# VOC_Board.net
KiCad netlist of a schematic drawn in Altium Designer
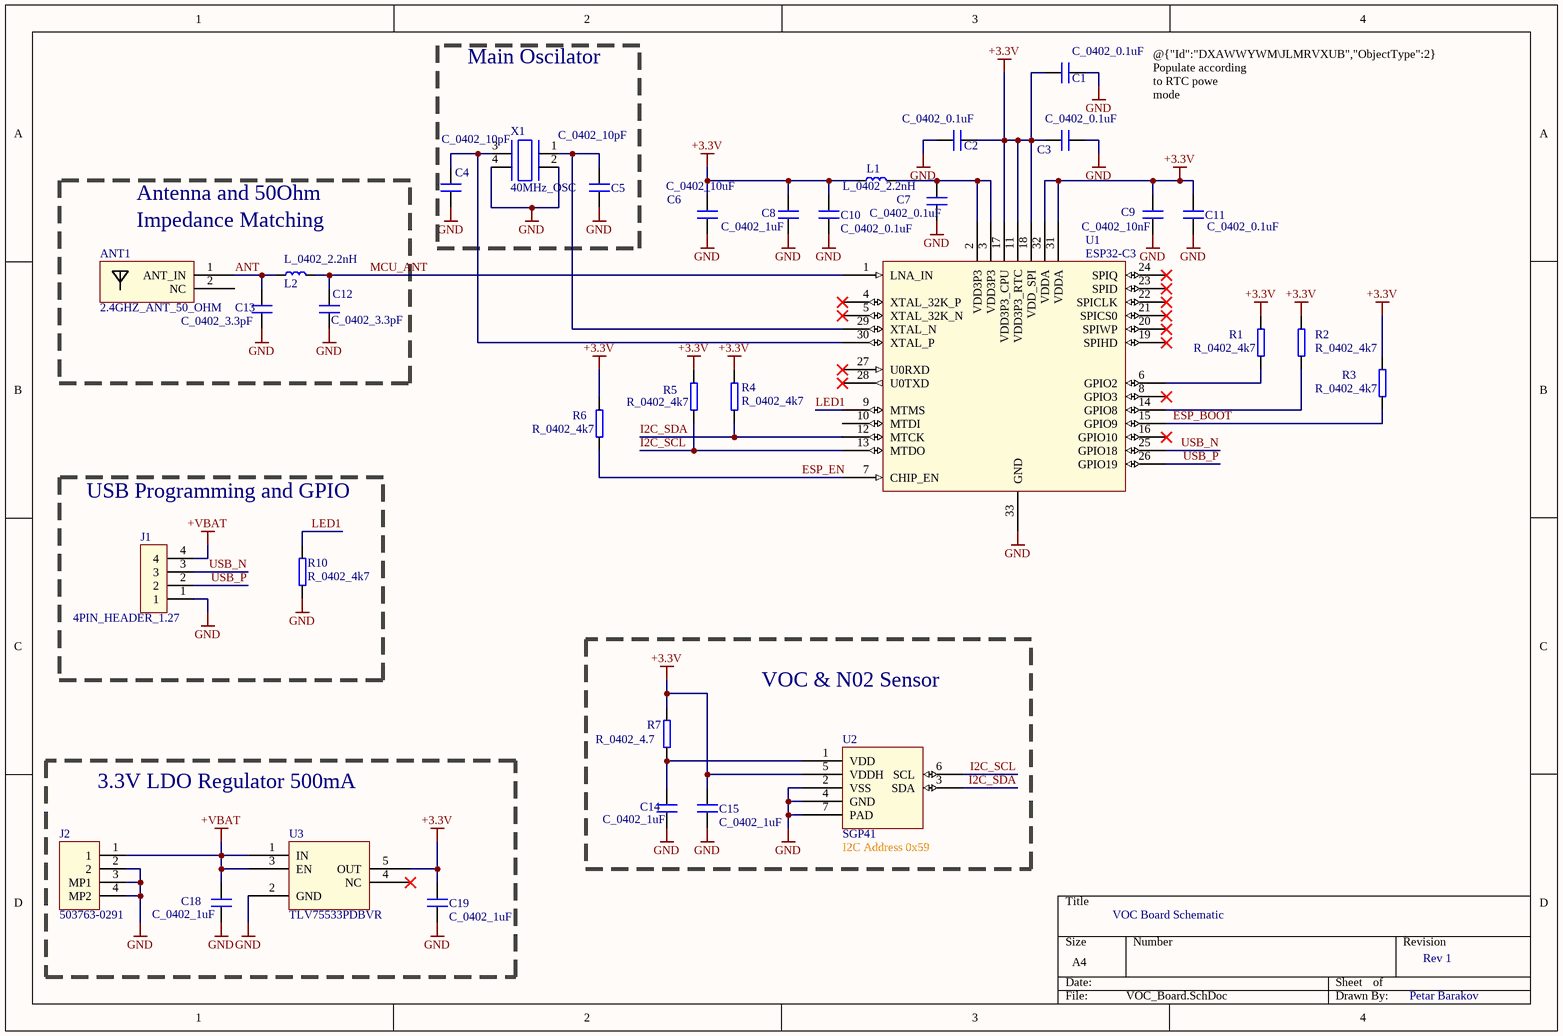
[diagram p0: VOC_Board.SchDoc]

(export (version "E")
  (design (tool "Eeschema 10.0.6"))
  (components
    (comp (ref "ANT1")
      (value "2.4GHZ_ANT_50_OHM")
      (footprint "Chip2PinSM127P600-8N")
      (description "2.4GHz Chip Antenna 50 Ohm Impedance ANT2012LL00R2400A")
      (libsource (lib "Petar B") (part "2.4GHZ_ANT_50_OHM"))
    )
    (comp (ref "C1")
      (value "C_0402_0.1uF")
      (footprint "C_0402")
      (fields (field (name "JLC PART NUMBER") "C1525"))
      (libsource (lib "Petar B") (part "Cap_symbol"))
    )
    (comp (ref "C2")
      (value "C_0402_0.1uF")
      (footprint "C_0402")
      (fields (field (name "JLC PART NUMBER") "C1525"))
      (libsource (lib "Petar B") (part "Cap_symbol"))
    )
    (comp (ref "C3")
      (value "C_0402_0.1uF")
      (footprint "C_0402")
      (fields (field (name "JLC PART NUMBER") "C1525"))
      (libsource (lib "Petar B") (part "Cap_symbol"))
    )
    (comp (ref "C4")
      (value "C_0402_10pF")
      (footprint "C_0402")
      (fields (field (name "JLC PART NUMBER") "C32949"))
      (libsource (lib "Petar B") (part "Cap_symbol"))
    )
    (comp (ref "C5")
      (value "C_0402_10pF")
      (footprint "C_0402")
      (fields (field (name "JLC PART NUMBER") "C32949"))
      (libsource (lib "Petar B") (part "Cap_symbol"))
    )
    (comp (ref "C6")
      (value "C_0402_10uF")
      (footprint "C_0402")
      (fields (field (name "JLC PART NUMBER") "C15525"))
      (libsource (lib "Petar B") (part "Cap_symbol"))
    )
    (comp (ref "C7")
      (value "C_0402_0.1uF")
      (footprint "C_0402")
      (fields (field (name "JLC PART NUMBER") "C1525"))
      (libsource (lib "Petar B") (part "Cap_symbol"))
    )
    (comp (ref "C8")
      (value "C_0402_1uF")
      (footprint "C_0402")
      (fields (field (name "JLC PART NUMBER") "C52923"))
      (libsource (lib "Petar B") (part "Cap_symbol"))
    )
    (comp (ref "C9")
      (value "C_0402_10nF")
      (footprint "C_0402")
      (fields (field (name "JLC PART NUMBER") "C15195"))
      (libsource (lib "Petar B") (part "Cap_symbol"))
    )
    (comp (ref "C10")
      (value "C_0402_0.1uF")
      (footprint "C_0402")
      (fields (field (name "JLC PART NUMBER") "C1525"))
      (libsource (lib "Petar B") (part "Cap_symbol"))
    )
    (comp (ref "C11")
      (value "C_0402_0.1uF")
      (footprint "C_0402")
      (fields (field (name "JLC PART NUMBER") "C1525"))
      (libsource (lib "Petar B") (part "Cap_symbol"))
    )
    (comp (ref "C12")
      (value "C_0402_3.3pF")
      (footprint "C_0402")
      (fields (field (name "JLC PART NUMBER") "C326841"))
      (libsource (lib "Petar B") (part "Cap_symbol"))
    )
    (comp (ref "C13")
      (value "C_0402_3.3pF")
      (footprint "C_0402")
      (fields (field (name "JLC PART NUMBER") "C326841"))
      (libsource (lib "Petar B") (part "Cap_symbol"))
    )
    (comp (ref "C14")
      (value "C_0402_1uF")
      (footprint "C_0402")
      (fields (field (name "JLC PART NUMBER") "C52923"))
      (libsource (lib "Petar B") (part "Cap_symbol"))
    )
    (comp (ref "C15")
      (value "C_0402_1uF")
      (footprint "C_0402")
      (fields (field (name "JLC PART NUMBER") "C52923"))
      (libsource (lib "Petar B") (part "Cap_symbol"))
    )
    (comp (ref "C18")
      (value "C_0402_1uF")
      (footprint "C_0402")
      (fields (field (name "JLC PART NUMBER") "C52923"))
      (libsource (lib "Petar B") (part "Cap_symbol"))
    )
    (comp (ref "C19")
      (value "C_0402_1uF")
      (footprint "C_0402")
      (fields (field (name "JLC PART NUMBER") "C52923"))
      (libsource (lib "Petar B") (part "Cap_symbol"))
    )
    (comp (ref "J1")
      (value "4PIN_HEADER_1.27")
      (footprint "4PIN_HEADER_1.27-Footprint-1")
      (libsource (lib "Petar B") (part "4PIN_HEADER_1.27-Symbol-1"))
    )
    (comp (ref "J2")
      (value "503763-0291")
      (footprint "Molex 503763-0291")
      (description "Molex 503763-0291")
      (libsource (lib "Petar B") (part "503763-0291"))
    )
    (comp (ref "L1")
      (value "L_0402_2.2nH")
      (footprint "L_0402")
      (fields (field (name "JLC PART NUMBER") "C92035"))
      (libsource (lib "Petar B") (part "Ind_Symbol"))
    )
    (comp (ref "L2")
      (value "L_0402_2.2nH")
      (footprint "L_0402")
      (fields (field (name "JLC PART NUMBER") "C92035"))
      (libsource (lib "Petar B") (part "Ind_Symbol"))
    )
    (comp (ref "R1")
      (value "R_0402_4k7")
      (footprint "R_0402")
      (fields (field (name "JLC PART NUMBER") "C25900"))
      (libsource (lib "Petar B") (part "R_symbol"))
    )
    (comp (ref "R2")
      (value "R_0402_4k7")
      (footprint "R_0402")
      (fields (field (name "JLC PART NUMBER") "C25900"))
      (libsource (lib "Petar B") (part "R_symbol"))
    )
    (comp (ref "R3")
      (value "R_0402_4k7")
      (footprint "R_0402")
      (fields (field (name "JLC PART NUMBER") "C25900"))
      (libsource (lib "Petar B") (part "R_symbol"))
    )
    (comp (ref "R4")
      (value "R_0402_4k7")
      (footprint "R_0402")
      (fields (field (name "JLC PART NUMBER") "C25900"))
      (libsource (lib "Petar B") (part "R_symbol"))
    )
    (comp (ref "R5")
      (value "R_0402_4k7")
      (footprint "R_0402")
      (fields (field (name "JLC PART NUMBER") "C25900"))
      (libsource (lib "Petar B") (part "R_symbol"))
    )
    (comp (ref "R6")
      (value "R_0402_4k7")
      (footprint "R_0402")
      (fields (field (name "JLC PART NUMBER") "C25900"))
      (libsource (lib "Petar B") (part "R_symbol"))
    )
    (comp (ref "R7")
      (value "R_0402_4.7")
      (footprint "R_0402")
      (fields (field (name "JLC PART NUMBER") "C137962"))
      (libsource (lib "Petar B") (part "R_symbol"))
    )
    (comp (ref "R10")
      (value "R_0402_4k7")
      (footprint "R_0402")
      (fields (field (name "JLC PART NUMBER") "C25900"))
      (libsource (lib "Petar B") (part "R_symbol"))
    )
    (comp (ref "U1")
      (value "ESP32-C3")
      (footprint "QFN127P600-8N")
      (description "33 pin ESP32_C3 Microcontroller")
      (fields (field (name "JLC PART NUMBER") "C2858491"))
      (libsource (lib "Petar B") (part "ESP32-C3_symbol"))
    )
    (comp (ref "U2")
      (value "SGP41")
      (footprint "SGP41-D-R4-Footprint-2")
      (description "Air Quality Sensors VOC and NOx (MOX) Gas Pollutant Sensor")
      (fields (field (name "JLC PART NUMBER") "C3659325"))
      (libsource (lib "Petar B") (part "SGP41"))
    )
    (comp (ref "U3")
      (value "TLV75533PDBVR")
      (footprint "SOT95P280X145-5N")
      (fields (field (name "JLC PART NUMBER") "C404027"))
      (libsource (lib "Petar B") (part "TLV75533PDBVR-Symbol"))
    )
    (comp (ref "X1")
      (value "40MHz_OSC")
      (footprint "40MHz_OSC-Footprint-1")
      (description "40 MHZ Oscillator, 10pF load capacitance")
      (fields (field (name "JLC PART NUMBER") "C426988"))
      (libsource (lib "Petar B") (part "OSC_SYMB"))
    )
  )
  (nets
    (net (code "1") (name "+3.3V") (class "Default")
      (node (ref "C1") (pin "1") (pinfunction "1_1") (pintype "passive"))
      (node (ref "C10") (pin "1") (pinfunction "1_1") (pintype "passive"))
      (node (ref "C11") (pin "2") (pinfunction "2_2") (pintype "passive"))
      (node (ref "C15") (pin "2") (pinfunction "2_2") (pintype "passive"))
      (node (ref "C19") (pin "2") (pinfunction "2_2") (pintype "passive"))
      (node (ref "C2") (pin "2") (pinfunction "2_2") (pintype "passive"))
      (node (ref "C3") (pin "1") (pinfunction "1_1") (pintype "passive"))
      (node (ref "C6") (pin "2") (pinfunction "2_2") (pintype "passive"))
      (node (ref "C8") (pin "2") (pinfunction "2_2") (pintype "passive"))
      (node (ref "C9") (pin "2") (pinfunction "2_2") (pintype "passive"))
      (node (ref "L1") (pin "1") (pinfunction "1_1") (pintype "passive"))
      (node (ref "R1") (pin "1") (pinfunction "1_1") (pintype "passive"))
      (node (ref "R2") (pin "1") (pinfunction "1_1") (pintype "passive"))
      (node (ref "R3") (pin "1") (pinfunction "1_1") (pintype "passive"))
      (node (ref "R4") (pin "1") (pinfunction "1_1") (pintype "passive"))
      (node (ref "R5") (pin "1") (pinfunction "1_1") (pintype "passive"))
      (node (ref "R6") (pin "1") (pinfunction "1_1") (pintype "passive"))
      (node (ref "R7") (pin "1") (pinfunction "1_1") (pintype "passive"))
      (node (ref "U1") (pin "11") (pinfunction "VDD3P3_RTC_11") (pintype "power_in"))
      (node (ref "U1") (pin "17") (pinfunction "VDD3P3_CPU_17") (pintype "power_in"))
      (node (ref "U1") (pin "18") (pinfunction "VDD_SPI_18") (pintype "power_in"))
      (node (ref "U1") (pin "31") (pinfunction "VDDA_31") (pintype "power_in"))
      (node (ref "U1") (pin "32") (pinfunction "VDDA_32") (pintype "power_in"))
      (node (ref "U2") (pin "5") (pinfunction "VDDH_5") (pintype "power_in"))
      (node (ref "U3") (pin "5") (pinfunction "OUT_5") (pintype "passive"))
    )
    (net (code "2") (name "+VBAT") (class "Default")
      (node (ref "C18") (pin "2") (pinfunction "2_2") (pintype "passive"))
      (node (ref "J1") (pin "4") (pinfunction "4_4") (pintype "passive"))
      (node (ref "J2") (pin "1") (pinfunction "1_1") (pintype "passive"))
      (node (ref "U3") (pin "1") (pinfunction "IN_1") (pintype "passive"))
      (node (ref "U3") (pin "3") (pinfunction "EN_3") (pintype "passive"))
    )
    (net (code "3") (name "/ANT") (class "Default")
      (node (ref "ANT1") (pin "1") (pinfunction "ANT_IN_1") (pintype "passive"))
      (node (ref "C13") (pin "2") (pinfunction "2_2") (pintype "passive"))
      (node (ref "L2") (pin "1") (pinfunction "1_1") (pintype "passive"))
    )
    (net (code "4") (name "/ESP_BOOT") (class "Default")
      (node (ref "R3") (pin "2") (pinfunction "2_2") (pintype "passive"))
      (node (ref "U1") (pin "15") (pinfunction "GPIO9_15") (pintype "bidirectional"))
    )
    (net (code "5") (name "/ESP_EN") (class "Default")
      (node (ref "R6") (pin "2") (pinfunction "2_2") (pintype "passive"))
      (node (ref "U1") (pin "7") (pinfunction "CHIP_EN_7") (pintype "input"))
    )
    (net (code "6") (name "/I2C_SCL") (class "Default")
      (node (ref "R5") (pin "2") (pinfunction "2_2") (pintype "passive"))
      (node (ref "U1") (pin "13") (pinfunction "MTDO_13") (pintype "bidirectional"))
      (node (ref "U2") (pin "6") (pinfunction "SCL_6") (pintype "bidirectional"))
    )
    (net (code "7") (name "/I2C_SDA") (class "Default")
      (node (ref "R4") (pin "2") (pinfunction "2_2") (pintype "passive"))
      (node (ref "U1") (pin "12") (pinfunction "MTCK_12") (pintype "bidirectional"))
      (node (ref "U2") (pin "3") (pinfunction "SDA_3") (pintype "bidirectional"))
    )
    (net (code "8") (name "/LED1") (class "Default")
      (node (ref "R10") (pin "1") (pinfunction "1_1") (pintype "passive"))
      (node (ref "U1") (pin "9") (pinfunction "MTMS_9") (pintype "bidirectional"))
    )
    (net (code "9") (name "/MCU_ANT") (class "Default")
      (node (ref "C12") (pin "2") (pinfunction "2_2") (pintype "passive"))
      (node (ref "L2") (pin "2") (pinfunction "2_2") (pintype "passive"))
      (node (ref "U1") (pin "1") (pinfunction "LNA_IN_1") (pintype "input"))
    )
    (net (code "10") (name "/USB_N") (class "Default")
      (node (ref "J1") (pin "3") (pinfunction "3_3") (pintype "passive"))
      (node (ref "U1") (pin "25") (pinfunction "GPIO18_25") (pintype "bidirectional"))
    )
    (net (code "11") (name "/USB_P") (class "Default")
      (node (ref "J1") (pin "2") (pinfunction "2_2") (pintype "passive"))
      (node (ref "U1") (pin "26") (pinfunction "GPIO19_26") (pintype "bidirectional"))
    )
    (net (code "12") (name "GND") (class "Default")
      (node (ref "C1") (pin "2") (pinfunction "2_2") (pintype "passive"))
      (node (ref "C10") (pin "2") (pinfunction "2_2") (pintype "passive"))
      (node (ref "C11") (pin "1") (pinfunction "1_1") (pintype "passive"))
      (node (ref "C12") (pin "1") (pinfunction "1_1") (pintype "passive"))
      (node (ref "C13") (pin "1") (pinfunction "1_1") (pintype "passive"))
      (node (ref "C14") (pin "1") (pinfunction "1_1") (pintype "passive"))
      (node (ref "C15") (pin "1") (pinfunction "1_1") (pintype "passive"))
      (node (ref "C18") (pin "1") (pinfunction "1_1") (pintype "passive"))
      (node (ref "C19") (pin "1") (pinfunction "1_1") (pintype "passive"))
      (node (ref "C2") (pin "1") (pinfunction "1_1") (pintype "passive"))
      (node (ref "C3") (pin "2") (pinfunction "2_2") (pintype "passive"))
      (node (ref "C4") (pin "1") (pinfunction "1_1") (pintype "passive"))
      (node (ref "C5") (pin "1") (pinfunction "1_1") (pintype "passive"))
      (node (ref "C6") (pin "1") (pinfunction "1_1") (pintype "passive"))
      (node (ref "C7") (pin "2") (pinfunction "2_2") (pintype "passive"))
      (node (ref "C8") (pin "1") (pinfunction "1_1") (pintype "passive"))
      (node (ref "C9") (pin "1") (pinfunction "1_1") (pintype "passive"))
      (node (ref "J1") (pin "1") (pinfunction "1_1") (pintype "passive"))
      (node (ref "J2") (pin "2") (pinfunction "2_2") (pintype "passive"))
      (node (ref "J2") (pin "3") (pinfunction "MP1_3") (pintype "passive"))
      (node (ref "J2") (pin "4") (pinfunction "MP2_4") (pintype "passive"))
      (node (ref "R10") (pin "2") (pinfunction "2_2") (pintype "passive"))
      (node (ref "U1") (pin "33") (pinfunction "GND_33") (pintype "power_in"))
      (node (ref "U2") (pin "2") (pinfunction "VSS_2") (pintype "power_in"))
      (node (ref "U2") (pin "4") (pinfunction "GND_4") (pintype "passive"))
      (node (ref "U2") (pin "7") (pinfunction "PAD_7") (pintype "passive"))
      (node (ref "U3") (pin "2") (pinfunction "GND_2") (pintype "passive"))
      (node (ref "X1") (pin "2") (pinfunction "2_2") (pintype "passive"))
      (node (ref "X1") (pin "4") (pinfunction "4_4") (pintype "passive"))
    )
    (net (code "13") (name "Net-(C7-Pad1)") (class "Default")
      (node (ref "C7") (pin "1") (pinfunction "1_1") (pintype "passive"))
      (node (ref "L1") (pin "2") (pinfunction "2_2") (pintype "passive"))
      (node (ref "U1") (pin "2") (pinfunction "VDD3P3_2") (pintype "power_in"))
      (node (ref "U1") (pin "3") (pinfunction "VDD3P3_3") (pintype "power_in"))
    )
    (net (code "14") (name "Net-(U1-GPIO2)") (class "Default")
      (node (ref "R1") (pin "2") (pinfunction "2_2") (pintype "passive"))
      (node (ref "U1") (pin "6") (pinfunction "GPIO2_6") (pintype "bidirectional"))
    )
    (net (code "15") (name "Net-(U1-GPIO8)") (class "Default")
      (node (ref "R2") (pin "2") (pinfunction "2_2") (pintype "passive"))
      (node (ref "U1") (pin "14") (pinfunction "GPIO8_14") (pintype "bidirectional"))
    )
    (net (code "16") (name "Net-(U1-XTAL_N)") (class "Default")
      (node (ref "C5") (pin "2") (pinfunction "2_2") (pintype "passive"))
      (node (ref "U1") (pin "29") (pinfunction "XTAL_N_29") (pintype "bidirectional"))
      (node (ref "X1") (pin "1") (pinfunction "1_1") (pintype "passive"))
    )
    (net (code "17") (name "Net-(U1-XTAL_P)") (class "Default")
      (node (ref "C4") (pin "2") (pinfunction "2_2") (pintype "passive"))
      (node (ref "U1") (pin "30") (pinfunction "XTAL_P_30") (pintype "bidirectional"))
      (node (ref "X1") (pin "3") (pinfunction "3_3") (pintype "passive"))
    )
    (net (code "18") (name "Net-(U2-VDD)") (class "Default")
      (node (ref "C14") (pin "2") (pinfunction "2_2") (pintype "passive"))
      (node (ref "R7") (pin "2") (pinfunction "2_2") (pintype "passive"))
      (node (ref "U2") (pin "1") (pinfunction "VDD_1") (pintype "power_in"))
    )
    (net (code "19") (name "unconnected-(ANT1-NC-Pad2)") (class "Default")
      (node (ref "ANT1") (pin "2") (pinfunction "NC_2") (pintype "passive"))
    )
    (net (code "20") (name "unconnected-(U1-GPIO3-Pad8)") (class "Default")
      (node (ref "U1") (pin "8") (pinfunction "GPIO3_8") (pintype "bidirectional+no_connect"))
    )
    (net (code "21") (name "unconnected-(U1-GPIO10-Pad16)") (class "Default")
      (node (ref "U1") (pin "16") (pinfunction "GPIO10_16") (pintype "bidirectional+no_connect"))
    )
    (net (code "22") (name "unconnected-(U1-MTDI-Pad10)") (class "Default")
      (node (ref "U1") (pin "10") (pinfunction "MTDI_10") (pintype "bidirectional"))
    )
    (net (code "23") (name "unconnected-(U1-SPICLK-Pad22)") (class "Default")
      (node (ref "U1") (pin "22") (pinfunction "SPICLK_22") (pintype "bidirectional+no_connect"))
    )
    (net (code "24") (name "unconnected-(U1-SPICS0-Pad21)") (class "Default")
      (node (ref "U1") (pin "21") (pinfunction "SPICS0_21") (pintype "bidirectional+no_connect"))
    )
    (net (code "25") (name "unconnected-(U1-SPID-Pad23)") (class "Default")
      (node (ref "U1") (pin "23") (pinfunction "SPID_23") (pintype "bidirectional+no_connect"))
    )
    (net (code "26") (name "unconnected-(U1-SPIHD-Pad19)") (class "Default")
      (node (ref "U1") (pin "19") (pinfunction "SPIHD_19") (pintype "bidirectional+no_connect"))
    )
    (net (code "27") (name "unconnected-(U1-SPIQ-Pad24)") (class "Default")
      (node (ref "U1") (pin "24") (pinfunction "SPIQ_24") (pintype "bidirectional+no_connect"))
    )
    (net (code "28") (name "unconnected-(U1-SPIWP-Pad20)") (class "Default")
      (node (ref "U1") (pin "20") (pinfunction "SPIWP_20") (pintype "bidirectional+no_connect"))
    )
    (net (code "29") (name "unconnected-(U1-U0RXD-Pad27)") (class "Default")
      (node (ref "U1") (pin "27") (pinfunction "U0RXD_27") (pintype "input+no_connect"))
    )
    (net (code "30") (name "unconnected-(U1-U0TXD-Pad28)") (class "Default")
      (node (ref "U1") (pin "28") (pinfunction "U0TXD_28") (pintype "output+no_connect"))
    )
    (net (code "31") (name "unconnected-(U1-XTAL_32K_N-Pad5)") (class "Default")
      (node (ref "U1") (pin "5") (pinfunction "XTAL_32K_N_5") (pintype "bidirectional+no_connect"))
    )
    (net (code "32") (name "unconnected-(U1-XTAL_32K_P-Pad4)") (class "Default")
      (node (ref "U1") (pin "4") (pinfunction "XTAL_32K_P_4") (pintype "bidirectional+no_connect"))
    )
    (net (code "33") (name "unconnected-(U3-NC-Pad4)") (class "Default")
      (node (ref "U3") (pin "4") (pinfunction "NC_4") (pintype "passive+no_connect"))
    )
  )
)
